# mcu.net
KiCad netlist of a schematic drawn in Altium Designer
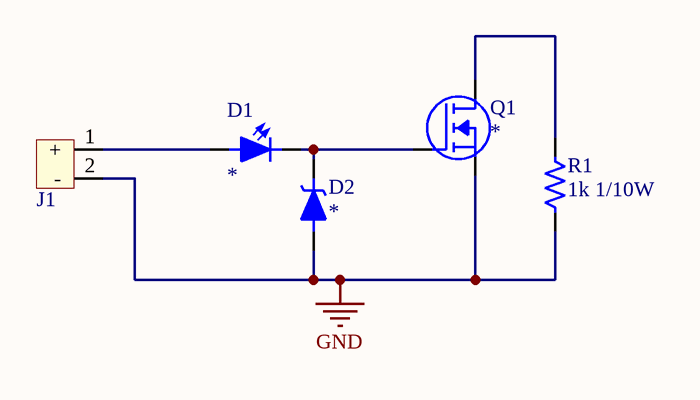
[diagram p0: mcu.SchDoc]

(export (version "E")
  (design (tool "Eeschema 10.0.6"))
  (components
    (comp (ref "D1")
      (value "LED")
      (footprint "LED_0603 IPC-A")
      (fields (field (name "ALTIUM_VALUE") "*"))
      (libsource (lib "altiumLib") (part "LED"))
    )
    (comp (ref "D2")
      (value "Zener diode")
      (footprint "SOD-323 IPC-C")
      (fields (field (name "ALTIUM_VALUE") "*"))
      (libsource (lib "altiumLib") (part "Zener diode"))
    )
    (comp (ref "J1")
      (value "2x1 Header")
      (footprint "2.54mm_1mm_1x2")
      (libsource (lib "altiumLib") (part "2x1 Header"))
    )
    (comp (ref "Q1")
      (value "E-MOSFET N")
      (footprint "SOT-23 IPC-C")
      (fields (field (name "ALTIUM_VALUE") "*"))
      (libsource (lib "altiumLib") (part "E-MOSFET N"))
    )
    (comp (ref "R1")
      (value "1k 1/10W")
      (footprint "RES_0805 IPC-C")
      (fields (field (name "Comment") "Resistor"))
      (libsource (lib "altiumLib") (part "Resistor"))
    )
  )
  (nets
    (net (code "1") (name "GND") (class "Default")
      (node (ref "D2") (pin "1") (pinfunction "A_1") (pintype "passive"))
      (node (ref "J1") (pin "2") (pinfunction "-_2") (pintype "passive"))
      (node (ref "Q1") (pin "2") (pinfunction "S_2") (pintype "passive"))
      (node (ref "R1") (pin "1") (pinfunction "1_1") (pintype "passive"))
    )
    (net (code "2") (name "Net-(D1-A)") (class "Default")
      (node (ref "D1") (pin "1") (pinfunction "A_1") (pintype "passive"))
      (node (ref "J1") (pin "1") (pinfunction "+_1") (pintype "passive"))
    )
    (net (code "3") (name "Net-(D1-K)") (class "Default")
      (node (ref "D1") (pin "2") (pinfunction "K_2") (pintype "passive"))
      (node (ref "D2") (pin "2") (pinfunction "K_2") (pintype "passive"))
      (node (ref "Q1") (pin "1") (pinfunction "G_1") (pintype "passive"))
    )
    (net (code "4") (name "Net-(Q1-D)") (class "Default")
      (node (ref "Q1") (pin "3") (pinfunction "D_3") (pintype "passive"))
      (node (ref "R1") (pin "2") (pinfunction "2_2") (pintype "passive"))
    )
  )
)
